# OctoWatchScheme.net
KiCad netlist of a schematic drawn in EAGLE
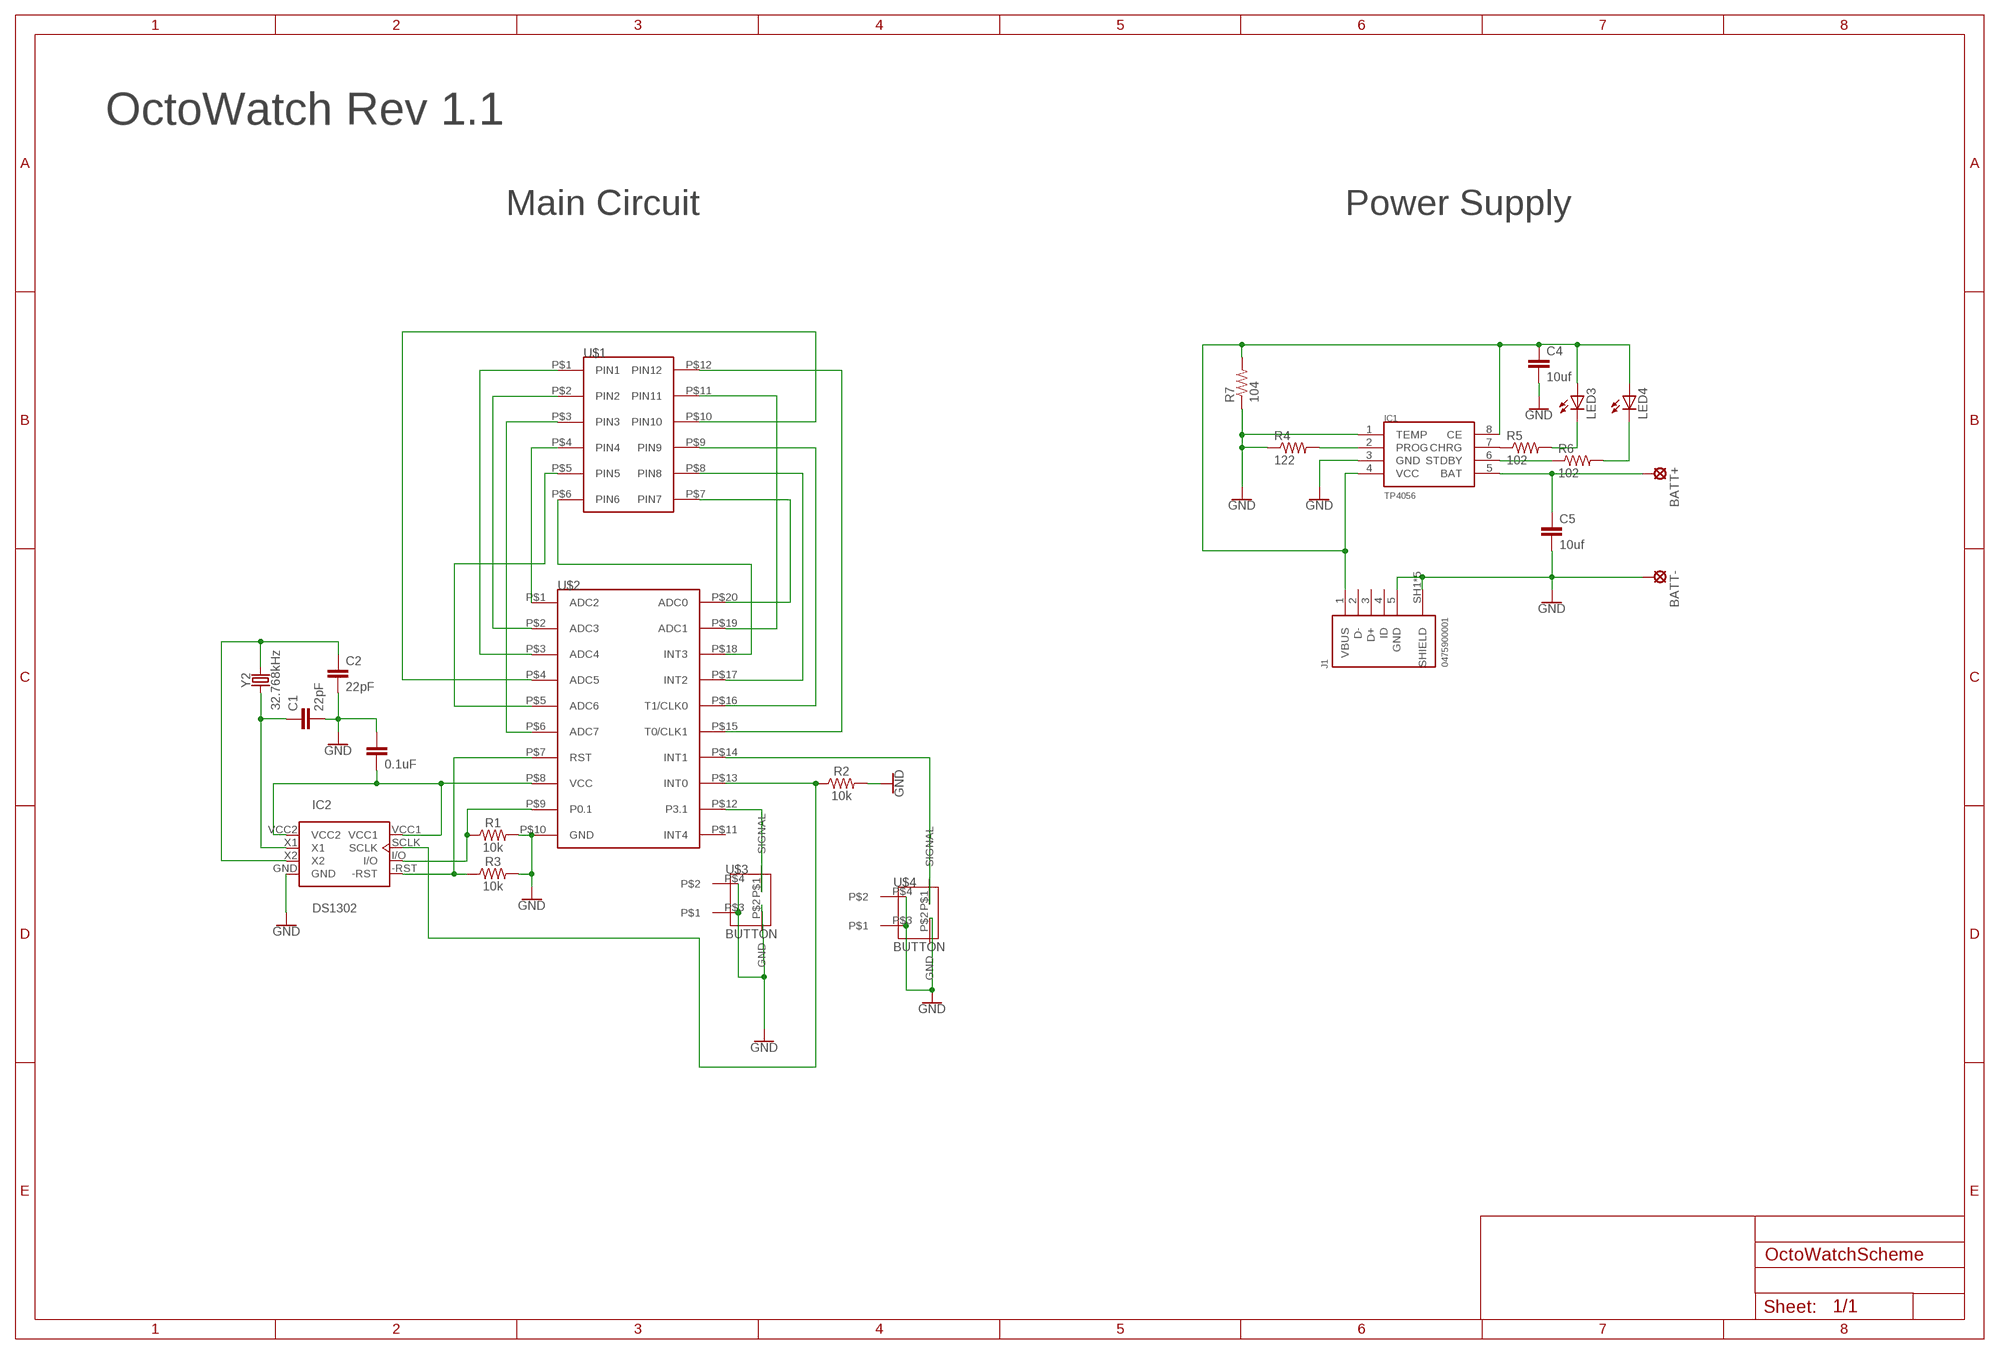
[diagram p0: schematic, sheet 1]

(export (version "E")
  (design (tool "Eeschema 10.0.6"))
  (components
    (comp (ref "BATT+")
      (value "LSP13")
      (footprint "eagle-import:LSP13")
      (libsource (lib "eagle-import") (part "LSP13"))
    )
    (comp (ref "BATT-")
      (value "LSP13")
      (footprint "eagle-import:LSP13")
      (libsource (lib "eagle-import") (part "LSP13"))
    )
    (comp (ref "C1")
      (value "22pF")
      (footprint "eagle-import:0402-TIGHT")
      (libsource (lib "eagle-import") (part "22PF-0402T-16V-10%"))
    )
    (comp (ref "C2")
      (value "22pF")
      (footprint "eagle-import:0402-TIGHT")
      (libsource (lib "eagle-import") (part "22PF-0402T-16V-10%"))
    )
    (comp (ref "C3")
      (value "0.1uF")
      (footprint "eagle-import:0402")
      (libsource (lib "eagle-import") (part "0.1UF-0402-6.3V-10%-X7R"))
    )
    (comp (ref "C4")
      (value "10uf")
      (footprint "eagle-import:C0805")
      (libsource (lib "eagle-import") (part "C-EUC0805"))
    )
    (comp (ref "C5")
      (value "10uf")
      (footprint "eagle-import:C0805")
      (libsource (lib "eagle-import") (part "C-EUC0805"))
    )
    (comp (ref "IC1")
      (value "TP4056")
      (footprint "eagle-import:SOP-8")
      (libsource (lib "eagle-import") (part "TP4056"))
    )
    (comp (ref "IC2")
      (value "DS1302")
      (footprint "eagle-import:DIL08")
      (libsource (lib "eagle-import") (part "DS1302"))
    )
    (comp (ref "J1")
      (value "0475900001")
      (footprint "eagle-import:0475900001")
      (fields
        (field (name "DIGIKEY_PARTNO") "WM17144TR-ND")
        (field (name "MANUFACTURER") "Molex")
        (field (name "CREATED_BY") "PCBLayout.com")
      )
      (libsource (lib "eagle-import") (part "0475900001"))
    )
    (comp (ref "LED3")
      (value "LEDCHIPLED_0603")
      (footprint "eagle-import:CHIPLED_0603")
      (libsource (lib "eagle-import") (part "LEDCHIPLED_0603"))
    )
    (comp (ref "LED4")
      (value "LEDCHIPLED_0603")
      (footprint "eagle-import:CHIPLED_0603")
      (libsource (lib "eagle-import") (part "LEDCHIPLED_0603"))
    )
    (comp (ref "R1")
      (value "10k")
      (footprint "eagle-import:0603")
      (libsource (lib "eagle-import") (part "10KOHM-0603-1/10W-1%"))
    )
    (comp (ref "R2")
      (value "10k")
      (footprint "eagle-import:0603")
      (libsource (lib "eagle-import") (part "10KOHM-0603-1/10W-1%"))
    )
    (comp (ref "R3")
      (value "10k")
      (footprint "eagle-import:0603")
      (libsource (lib "eagle-import") (part "10KOHM-0603-1/10W-1%"))
    )
    (comp (ref "R4")
      (value "122")
      (footprint "eagle-import:R0402")
      (libsource (lib "eagle-import") (part "R-US_R0402"))
    )
    (comp (ref "R5")
      (value "102")
      (footprint "eagle-import:R0402")
      (libsource (lib "eagle-import") (part "R-US_R0402"))
    )
    (comp (ref "R6")
      (value "102")
      (footprint "eagle-import:R0402")
      (libsource (lib "eagle-import") (part "R-US_R0402"))
    )
    (comp (ref "R7")
      (value "104")
      (footprint "eagle-import:R0805")
      (libsource (lib "eagle-import") (part "R-US_R0805"))
    )
    (comp (ref "U$1")
      (value "LED_SEGMENT")
      (footprint "eagle-import:LED_SEGMENT")
      (libsource (lib "eagle-import") (part "LED_SEGMENT"))
    )
    (comp (ref "U$2")
      (value "STC15F204AESTC15L204AE")
      (footprint "eagle-import:STC15F204AE2")
      (libsource (lib "eagle-import") (part "STC15F204AESTC15L204AE"))
    )
    (comp (ref "U$3")
      (value "BUTTON")
      (footprint "eagle-import:BUTTON")
      (libsource (lib "eagle-import") (part "BUTTON"))
    )
    (comp (ref "U$4")
      (value "BUTTON")
      (footprint "eagle-import:BUTTON")
      (libsource (lib "eagle-import") (part "BUTTON"))
    )
    (comp (ref "Y2")
      (value "32.768kHz")
      (footprint "eagle-import:CRYSTAL-PTH-2X6-CYL")
      (libsource (lib "eagle-import") (part "CRYSTAL-32.768KHZPTH-2X6"))
    )
  )
  (nets
    (net (code "1") (name "GND") (class "Default")
      (node (ref "BATT-") (pin "MP") (pinfunction "MP_MP") (pintype "passive"))
      (node (ref "C1") (pin "2") (pinfunction "2_2") (pintype "passive"))
      (node (ref "C2") (pin "2") (pinfunction "2_2") (pintype "passive"))
      (node (ref "C3") (pin "1") (pinfunction "1_1") (pintype "passive"))
      (node (ref "C4") (pin "2") (pinfunction "2_2") (pintype "passive"))
      (node (ref "C5") (pin "2") (pinfunction "2_2") (pintype "passive"))
      (node (ref "IC1") (pin "1") (pinfunction "TEMP_1") (pintype "bidirectional"))
      (node (ref "IC1") (pin "3") (pinfunction "GND_3") (pintype "bidirectional"))
      (node (ref "IC2") (pin "GND") (pinfunction "GND_GND") (pintype "passive"))
      (node (ref "J1") (pin "5") (pinfunction "GND_5") (pintype "passive"))
      (node (ref "J1") (pin "SH1") (pinfunction "SHIELD_SH1") (pintype "power_in"))
      (node (ref "J1") (pin "SH2") (pinfunction "SHIELD_SH2") (pintype "power_in"))
      (node (ref "J1") (pin "SH3") (pinfunction "SHIELD_SH3") (pintype "power_in"))
      (node (ref "J1") (pin "SH4") (pinfunction "SHIELD_SH4") (pintype "power_in"))
      (node (ref "J1") (pin "SH5") (pinfunction "SHIELD_SH5") (pintype "power_in"))
      (node (ref "R1") (pin "2") (pinfunction "2_2") (pintype "passive"))
      (node (ref "R2") (pin "2") (pinfunction "2_2") (pintype "passive"))
      (node (ref "R3") (pin "2") (pinfunction "2_2") (pintype "passive"))
      (node (ref "R4") (pin "1") (pinfunction "1_1") (pintype "passive"))
      (node (ref "R7") (pin "1") (pinfunction "1_1") (pintype "passive"))
      (node (ref "U$2") (pin "P$10") (pinfunction "GND_P$10") (pintype "bidirectional"))
      (node (ref "U$3") (pin "P$2") (pinfunction "GND_P$2") (pintype "bidirectional"))
      (node (ref "U$3") (pin "P$3") (pinfunction "P$1_P$3") (pintype "bidirectional"))
      (node (ref "U$3") (pin "P$4") (pinfunction "P$2_P$4") (pintype "bidirectional"))
      (node (ref "U$4") (pin "P$2") (pinfunction "GND_P$2") (pintype "bidirectional"))
      (node (ref "U$4") (pin "P$3") (pinfunction "P$1_P$3") (pintype "bidirectional"))
      (node (ref "U$4") (pin "P$4") (pinfunction "P$2_P$4") (pintype "bidirectional"))
    )
    (net (code "2") (name "Net-(C1-Pad1)") (class "Default")
      (node (ref "C1") (pin "1") (pinfunction "1_1") (pintype "passive"))
      (node (ref "IC2") (pin "X1") (pinfunction "X1_X1") (pintype "tri_state"))
      (node (ref "Y2") (pin "1") (pinfunction "1_1") (pintype "passive"))
    )
    (net (code "3") (name "Net-(C2-Pad1)") (class "Default")
      (node (ref "C2") (pin "1") (pinfunction "1_1") (pintype "passive"))
      (node (ref "IC2") (pin "X2") (pinfunction "X2_X2") (pintype "tri_state"))
      (node (ref "Y2") (pin "2") (pinfunction "2_2") (pintype "passive"))
    )
    (net (code "4") (name "Net-(IC1-BAT)") (class "Default")
      (node (ref "BATT+") (pin "MP") (pinfunction "MP_MP") (pintype "passive"))
      (node (ref "C5") (pin "1") (pinfunction "1_1") (pintype "passive"))
      (node (ref "IC1") (pin "5") (pinfunction "BAT_5") (pintype "bidirectional"))
    )
    (net (code "5") (name "Net-(IC1-CE)") (class "Default")
      (node (ref "C4") (pin "1") (pinfunction "1_1") (pintype "passive"))
      (node (ref "IC1") (pin "4") (pinfunction "VCC_4") (pintype "bidirectional"))
      (node (ref "IC1") (pin "8") (pinfunction "CE_8") (pintype "bidirectional"))
      (node (ref "J1") (pin "1") (pinfunction "VBUS_1") (pintype "passive"))
      (node (ref "LED3") (pin "A") (pinfunction "A_A") (pintype "passive"))
      (node (ref "LED4") (pin "A") (pinfunction "A_A") (pintype "passive"))
      (node (ref "R7") (pin "2") (pinfunction "2_2") (pintype "passive"))
    )
    (net (code "6") (name "Net-(IC1-CHRG)") (class "Default")
      (node (ref "IC1") (pin "7") (pinfunction "CHRG_7") (pintype "bidirectional"))
      (node (ref "R5") (pin "1") (pinfunction "1_1") (pintype "passive"))
    )
    (net (code "7") (name "Net-(IC1-PROG)") (class "Default")
      (node (ref "IC1") (pin "2") (pinfunction "PROG_2") (pintype "bidirectional"))
      (node (ref "R4") (pin "2") (pinfunction "2_2") (pintype "passive"))
    )
    (net (code "8") (name "Net-(IC1-STDBY)") (class "Default")
      (node (ref "IC1") (pin "6") (pinfunction "STDBY_6") (pintype "bidirectional"))
      (node (ref "R6") (pin "1") (pinfunction "1_1") (pintype "passive"))
    )
    (net (code "9") (name "Net-(LED3-PadC)") (class "Default")
      (node (ref "LED3") (pin "C") (pinfunction "C_C") (pintype "passive"))
      (node (ref "R5") (pin "2") (pinfunction "2_2") (pintype "passive"))
    )
    (net (code "10") (name "Net-(LED4-PadC)") (class "Default")
      (node (ref "LED4") (pin "C") (pinfunction "C_C") (pintype "passive"))
      (node (ref "R6") (pin "2") (pinfunction "2_2") (pintype "passive"))
    )
    (net (code "11") (name "Net-(U$1-PIN1)") (class "Default")
      (node (ref "U$1") (pin "P$1") (pinfunction "PIN1_P$1") (pintype "bidirectional"))
      (node (ref "U$2") (pin "P$3") (pinfunction "ADC4_P$3") (pintype "bidirectional"))
    )
    (net (code "12") (name "Net-(U$1-PIN2)") (class "Default")
      (node (ref "U$1") (pin "P$2") (pinfunction "PIN2_P$2") (pintype "bidirectional"))
      (node (ref "U$2") (pin "P$2") (pinfunction "ADC3_P$2") (pintype "bidirectional"))
    )
    (net (code "13") (name "Net-(U$1-PIN3)") (class "Default")
      (node (ref "U$1") (pin "P$3") (pinfunction "PIN3_P$3") (pintype "bidirectional"))
      (node (ref "U$2") (pin "P$6") (pinfunction "ADC7_P$6") (pintype "bidirectional"))
    )
    (net (code "14") (name "Net-(U$1-PIN4)") (class "Default")
      (node (ref "U$1") (pin "P$4") (pinfunction "PIN4_P$4") (pintype "bidirectional"))
      (node (ref "U$2") (pin "P$1") (pinfunction "ADC2_P$1") (pintype "bidirectional"))
    )
    (net (code "15") (name "Net-(U$1-PIN5)") (class "Default")
      (node (ref "U$1") (pin "P$5") (pinfunction "PIN5_P$5") (pintype "bidirectional"))
      (node (ref "U$2") (pin "P$5") (pinfunction "ADC6_P$5") (pintype "bidirectional"))
    )
    (net (code "16") (name "Net-(U$1-PIN6)") (class "Default")
      (node (ref "U$1") (pin "P$6") (pinfunction "PIN6_P$6") (pintype "bidirectional"))
      (node (ref "U$2") (pin "P$18") (pinfunction "INT3_P$18") (pintype "bidirectional"))
    )
    (net (code "17") (name "Net-(U$1-PIN7)") (class "Default")
      (node (ref "U$1") (pin "P$7") (pinfunction "PIN7_P$7") (pintype "bidirectional"))
      (node (ref "U$2") (pin "P$20") (pinfunction "ADC0_P$20") (pintype "bidirectional"))
    )
    (net (code "18") (name "Net-(U$1-PIN8)") (class "Default")
      (node (ref "U$1") (pin "P$8") (pinfunction "PIN8_P$8") (pintype "bidirectional"))
      (node (ref "U$2") (pin "P$17") (pinfunction "INT2_P$17") (pintype "bidirectional"))
    )
    (net (code "19") (name "Net-(U$1-PIN9)") (class "Default")
      (node (ref "U$1") (pin "P$9") (pinfunction "PIN9_P$9") (pintype "bidirectional"))
      (node (ref "U$2") (pin "P$16") (pinfunction "T1/CLK0_P$16") (pintype "bidirectional"))
    )
    (net (code "20") (name "Net-(U$1-PIN10)") (class "Default")
      (node (ref "U$1") (pin "P$10") (pinfunction "PIN10_P$10") (pintype "bidirectional"))
      (node (ref "U$2") (pin "P$4") (pinfunction "ADC5_P$4") (pintype "bidirectional"))
    )
    (net (code "21") (name "Net-(U$1-PIN11)") (class "Default")
      (node (ref "U$1") (pin "P$11") (pinfunction "PIN11_P$11") (pintype "bidirectional"))
      (node (ref "U$2") (pin "P$19") (pinfunction "ADC1_P$19") (pintype "bidirectional"))
    )
    (net (code "22") (name "Net-(U$1-PIN12)") (class "Default")
      (node (ref "U$1") (pin "P$12") (pinfunction "PIN12_P$12") (pintype "bidirectional"))
      (node (ref "U$2") (pin "P$15") (pinfunction "T0/CLK1_P$15") (pintype "bidirectional"))
    )
    (net (code "23") (name "Net-(U$2-INT0)") (class "Default")
      (node (ref "IC2") (pin "SCLK") (pinfunction "SCLK_SCLK") (pintype "tri_state"))
      (node (ref "R2") (pin "1") (pinfunction "1_1") (pintype "passive"))
      (node (ref "U$2") (pin "P$13") (pinfunction "INT0_P$13") (pintype "bidirectional"))
    )
    (net (code "24") (name "Net-(U$2-INT1)") (class "Default")
      (node (ref "U$2") (pin "P$14") (pinfunction "INT1_P$14") (pintype "bidirectional"))
      (node (ref "U$4") (pin "P$1") (pinfunction "SIGNAL_P$1") (pintype "bidirectional"))
    )
    (net (code "25") (name "Net-(U$2-P0.1)") (class "Default")
      (node (ref "IC2") (pin "I/O") (pinfunction "I/O_I/O") (pintype "bidirectional"))
      (node (ref "R1") (pin "1") (pinfunction "1_1") (pintype "passive"))
      (node (ref "U$2") (pin "P$9") (pinfunction "P0.1_P$9") (pintype "bidirectional"))
    )
    (net (code "26") (name "Net-(U$2-P3.1)") (class "Default")
      (node (ref "U$2") (pin "P$12") (pinfunction "P3.1_P$12") (pintype "bidirectional"))
      (node (ref "U$3") (pin "P$1") (pinfunction "SIGNAL_P$1") (pintype "bidirectional"))
    )
    (net (code "27") (name "Net-(U$2-RST)") (class "Default")
      (node (ref "IC2") (pin "-RST") (pinfunction "-RST_-RST") (pintype "bidirectional"))
      (node (ref "R3") (pin "1") (pinfunction "1_1") (pintype "passive"))
      (node (ref "U$2") (pin "P$7") (pinfunction "RST_P$7") (pintype "bidirectional"))
    )
    (net (code "28") (name "Net-(U$2-VCC)") (class "Default")
      (node (ref "C3") (pin "2") (pinfunction "2_2") (pintype "passive"))
      (node (ref "IC2") (pin "VCC1") (pinfunction "VCC1_VCC1") (pintype "power_in"))
      (node (ref "IC2") (pin "VCC2") (pinfunction "VCC2_VCC2") (pintype "power_in"))
      (node (ref "U$2") (pin "P$8") (pinfunction "VCC_P$8") (pintype "bidirectional"))
    )
    (net (code "29") (name "unconnected-(J1-D+-Pad3)") (class "Default")
      (node (ref "J1") (pin "3") (pinfunction "D+_3") (pintype "passive"))
    )
    (net (code "30") (name "unconnected-(J1-D--Pad2)") (class "Default")
      (node (ref "J1") (pin "2") (pinfunction "D-_2") (pintype "passive"))
    )
    (net (code "31") (name "unconnected-(J1-ID-Pad4)") (class "Default")
      (node (ref "J1") (pin "4") (pinfunction "ID_4") (pintype "passive"))
    )
    (net (code "32") (name "unconnected-(U$2-INT4-PadP$11)") (class "Default")
      (node (ref "U$2") (pin "P$11") (pinfunction "INT4_P$11") (pintype "bidirectional"))
    )
  )
)
